# USB-PS2_v4_2.net
KiCad netlist of a schematic drawn in EAGLE
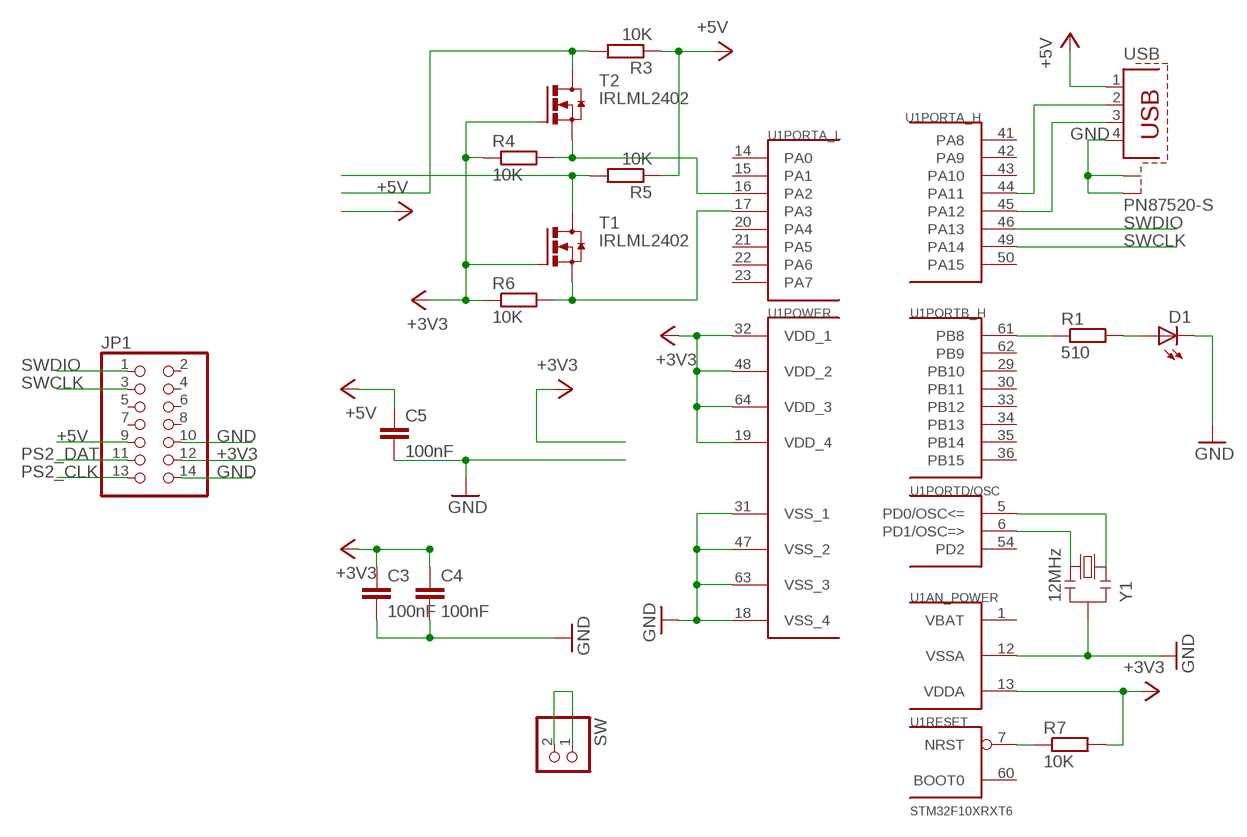
[diagram p0: schematic, sheet 1]

(export (version "E")
  (design (tool "Eeschema 10.0.6"))
  (components
    (comp (ref "C3")
      (value "100nF")
      (footprint "eagle-import:C0805")
      (libsource (lib "eagle-import") (part "C-EUC0805"))
    )
    (comp (ref "C4")
      (value "100nF")
      (footprint "eagle-import:C0805")
      (libsource (lib "eagle-import") (part "C-EUC0805"))
    )
    (comp (ref "C5")
      (value "100nF")
      (footprint "eagle-import:C0805")
      (libsource (lib "eagle-import") (part "C-EUC0805"))
    )
    (comp (ref "D1")
      (value "LEDSML0805")
      (footprint "eagle-import:SML0805")
      (libsource (lib "eagle-import") (part "LEDSML0805"))
    )
    (comp (ref "JP1")
      (value "PINHD-2X7")
      (footprint "eagle-import:2X07")
      (libsource (lib "eagle-import") (part "PINHD-2X7"))
    )
    (comp (ref "R1")
      (value "510")
      (footprint "eagle-import:R0805")
      (libsource (lib "eagle-import") (part "R-EU_R0805"))
    )
    (comp (ref "R3")
      (value "10K")
      (footprint "eagle-import:R0805")
      (libsource (lib "eagle-import") (part "R-EU_R0805"))
    )
    (comp (ref "R4")
      (value "10K")
      (footprint "eagle-import:R0805")
      (libsource (lib "eagle-import") (part "R-EU_R0805"))
    )
    (comp (ref "R5")
      (value "10K")
      (footprint "eagle-import:R0805")
      (libsource (lib "eagle-import") (part "R-EU_R0805"))
    )
    (comp (ref "R6")
      (value "10K")
      (footprint "eagle-import:R0805")
      (libsource (lib "eagle-import") (part "R-EU_R0805"))
    )
    (comp (ref "R7")
      (value "10K")
      (footprint "eagle-import:R0805")
      (libsource (lib "eagle-import") (part "R-EU_R0805"))
    )
    (comp (ref "SW")
      (value "PINHD-1X2")
      (footprint "eagle-import:1X02")
      (libsource (lib "eagle-import") (part "PINHD-1X2"))
    )
    (comp (ref "T1")
      (value "IRLML2402")
      (footprint "eagle-import:MICRO3")
      (libsource (lib "eagle-import") (part "IRLML2402"))
    )
    (comp (ref "T2")
      (value "IRLML2402")
      (footprint "eagle-import:MICRO3")
      (libsource (lib "eagle-import") (part "IRLML2402"))
    )
    (comp (ref "U1")
      (value "STM32F10XRXT6")
      (footprint "eagle-import:TQFP64")
      (libsource (lib "eagle-import") (part "STM32F10XRXT6"))
    )
    (comp (ref "USB")
      (value "PN87520-S")
      (footprint "eagle-import:PN87520-S")
      (libsource (lib "eagle-import") (part "PN87520-S"))
    )
    (comp (ref "Y1")
      (value "12MHz")
      (footprint "eagle-import:RESONATOR")
      (fields (field (name "PART_NUMBER") "CSTCE16M0V53-R0"))
      (libsource (lib "eagle-import") (part "0011_CSTCE16M0V53-R0"))
    )
  )
  (nets
    (net (code "1") (name "+3V3") (class "Default")
      (node (ref "C3") (pin "1") (pinfunction "1_1") (pintype "passive"))
      (node (ref "C4") (pin "1") (pinfunction "1_1") (pintype "passive"))
      (node (ref "JP1") (pin "12") (pinfunction "12_12") (pintype "passive"))
      (node (ref "R4") (pin "1") (pinfunction "1_1") (pintype "passive"))
      (node (ref "R6") (pin "1") (pinfunction "1_1") (pintype "passive"))
      (node (ref "R7") (pin "2") (pinfunction "2_2") (pintype "passive"))
      (node (ref "T1") (pin "1") (pinfunction "G_1") (pintype "passive"))
      (node (ref "T2") (pin "1") (pinfunction "G_1") (pintype "passive"))
      (node (ref "U1") (pin "13") (pinfunction "VDDA_13") (pintype "power_in"))
      (node (ref "U1") (pin "19") (pinfunction "VDD_4_19") (pintype "power_in"))
      (node (ref "U1") (pin "32") (pinfunction "VDD_1_32") (pintype "power_in"))
      (node (ref "U1") (pin "48") (pinfunction "VDD_2_48") (pintype "power_in"))
      (node (ref "U1") (pin "64") (pinfunction "VDD_3_64") (pintype "power_in"))
    )
    (net (code "2") (name "+5V") (class "Default")
      (node (ref "C5") (pin "1") (pinfunction "1_1") (pintype "passive"))
      (node (ref "JP1") (pin "9") (pinfunction "9_9") (pintype "passive"))
      (node (ref "R3") (pin "1") (pinfunction "1_1") (pintype "passive"))
      (node (ref "R5") (pin "1") (pinfunction "1_1") (pintype "passive"))
      (node (ref "USB") (pin "1") (pinfunction "1_1") (pintype "passive"))
    )
    (net (code "3") (name "/PS2_CLK") (class "Default")
      (node (ref "JP1") (pin "13") (pinfunction "13_13") (pintype "passive"))
      (node (ref "R5") (pin "2") (pinfunction "2_2") (pintype "passive"))
      (node (ref "T1") (pin "3") (pinfunction "D_3") (pintype "passive"))
    )
    (net (code "4") (name "/PS2_DAT") (class "Default")
      (node (ref "JP1") (pin "11") (pinfunction "11_11") (pintype "passive"))
      (node (ref "R3") (pin "2") (pinfunction "2_2") (pintype "passive"))
      (node (ref "T2") (pin "3") (pinfunction "D_3") (pintype "passive"))
    )
    (net (code "5") (name "/SWCLK") (class "Default")
      (node (ref "JP1") (pin "3") (pinfunction "3_3") (pintype "passive"))
      (node (ref "U1") (pin "49") (pinfunction "PA14_49") (pintype "bidirectional"))
    )
    (net (code "6") (name "/SWDIO") (class "Default")
      (node (ref "JP1") (pin "1") (pinfunction "1_1") (pintype "passive"))
      (node (ref "U1") (pin "46") (pinfunction "PA13_46") (pintype "bidirectional"))
    )
    (net (code "7") (name "/VBAT") (class "Default")
      (node (ref "U1") (pin "1") (pinfunction "VBAT_1") (pintype "power_in"))
    )
    (net (code "8") (name "GND") (class "Default")
      (node (ref "C3") (pin "2") (pinfunction "2_2") (pintype "passive"))
      (node (ref "C4") (pin "2") (pinfunction "2_2") (pintype "passive"))
      (node (ref "C5") (pin "2") (pinfunction "2_2") (pintype "passive"))
      (node (ref "D1") (pin "C") (pinfunction "C_C") (pintype "passive"))
      (node (ref "JP1") (pin "10") (pinfunction "10_10") (pintype "passive"))
      (node (ref "JP1") (pin "14") (pinfunction "14_14") (pintype "passive"))
      (node (ref "U1") (pin "12") (pinfunction "VSSA_12") (pintype "power_in"))
      (node (ref "U1") (pin "18") (pinfunction "VSS_4_18") (pintype "power_in"))
      (node (ref "U1") (pin "31") (pinfunction "VSS_1_31") (pintype "power_in"))
      (node (ref "U1") (pin "47") (pinfunction "VSS_2_47") (pintype "power_in"))
      (node (ref "U1") (pin "63") (pinfunction "VSS_3_63") (pintype "power_in"))
      (node (ref "USB") (pin "4") (pinfunction "4_4") (pintype "passive"))
      (node (ref "USB") (pin "S1") (pinfunction "S1_S1") (pintype "passive"))
      (node (ref "USB") (pin "S2") (pinfunction "S2_S2") (pintype "passive"))
      (node (ref "Y1") (pin "2") (pinfunction "2_2") (pintype "passive"))
    )
    (net (code "9") (name "Net-(D1-PadA)") (class "Default")
      (node (ref "D1") (pin "A") (pinfunction "A_A") (pintype "passive"))
      (node (ref "R1") (pin "2") (pinfunction "2_2") (pintype "passive"))
    )
    (net (code "10") (name "Net-(SW-Pad1)") (class "Default")
      (node (ref "SW") (pin "1") (pinfunction "1_1") (pintype "passive"))
      (node (ref "SW") (pin "2") (pinfunction "2_2") (pintype "passive"))
    )
    (net (code "11") (name "Net-(T1-S)") (class "Default")
      (node (ref "R6") (pin "2") (pinfunction "2_2") (pintype "passive"))
      (node (ref "T1") (pin "2") (pinfunction "S_2") (pintype "passive"))
      (node (ref "U1") (pin "17") (pinfunction "PA3_17") (pintype "bidirectional"))
    )
    (net (code "12") (name "Net-(T2-S)") (class "Default")
      (node (ref "R4") (pin "2") (pinfunction "2_2") (pintype "passive"))
      (node (ref "T2") (pin "2") (pinfunction "S_2") (pintype "passive"))
      (node (ref "U1") (pin "16") (pinfunction "PA2_16") (pintype "bidirectional"))
    )
    (net (code "13") (name "Net-(U1B-PA11)") (class "Default")
      (node (ref "U1") (pin "44") (pinfunction "PA11_44") (pintype "bidirectional"))
      (node (ref "USB") (pin "2") (pinfunction "2_2") (pintype "passive"))
    )
    (net (code "14") (name "Net-(U1B-PA12)") (class "Default")
      (node (ref "U1") (pin "45") (pinfunction "PA12_45") (pintype "bidirectional"))
      (node (ref "USB") (pin "3") (pinfunction "3_3") (pintype "passive"))
    )
    (net (code "15") (name "Net-(U1D-PB8)") (class "Default")
      (node (ref "R1") (pin "1") (pinfunction "1_1") (pintype "passive"))
      (node (ref "U1") (pin "61") (pinfunction "PB8_61") (pintype "bidirectional"))
    )
    (net (code "16") (name "Net-(U1H-PD0{slash}OSC<=)") (class "Default")
      (node (ref "U1") (pin "5") (pinfunction "PD0/OSC<=_5") (pintype "bidirectional"))
      (node (ref "Y1") (pin "1") (pinfunction "1_1") (pintype "passive"))
    )
    (net (code "17") (name "Net-(U1H-PD1{slash}OSC=>)") (class "Default")
      (node (ref "U1") (pin "6") (pinfunction "PD1/OSC=>_6") (pintype "bidirectional"))
      (node (ref "Y1") (pin "3") (pinfunction "3_3") (pintype "passive"))
    )
    (net (code "18") (name "Net-(U1J-NRST)") (class "Default")
      (node (ref "R7") (pin "1") (pinfunction "1_1") (pintype "passive"))
      (node (ref "U1") (pin "7") (pinfunction "NRST_7") (pintype "input"))
    )
    (net (code "19") (name "unconnected-(JP1-Pad2)") (class "Default")
      (node (ref "JP1") (pin "2") (pinfunction "2_2") (pintype "passive"))
    )
    (net (code "20") (name "unconnected-(JP1-Pad4)") (class "Default")
      (node (ref "JP1") (pin "4") (pinfunction "4_4") (pintype "passive"))
    )
    (net (code "21") (name "unconnected-(JP1-Pad5)") (class "Default")
      (node (ref "JP1") (pin "5") (pinfunction "5_5") (pintype "passive"))
    )
    (net (code "22") (name "unconnected-(JP1-Pad6)") (class "Default")
      (node (ref "JP1") (pin "6") (pinfunction "6_6") (pintype "passive"))
    )
    (net (code "23") (name "unconnected-(JP1-Pad7)") (class "Default")
      (node (ref "JP1") (pin "7") (pinfunction "7_7") (pintype "passive"))
    )
    (net (code "24") (name "unconnected-(JP1-Pad8)") (class "Default")
      (node (ref "JP1") (pin "8") (pinfunction "8_8") (pintype "passive"))
    )
    (net (code "25") (name "unconnected-(U1B-PA8-Pad41)") (class "Default")
      (node (ref "U1") (pin "41") (pinfunction "PA8_41") (pintype "bidirectional"))
    )
    (net (code "26") (name "unconnected-(U1B-PA9-Pad42)") (class "Default")
      (node (ref "U1") (pin "42") (pinfunction "PA9_42") (pintype "bidirectional"))
    )
    (net (code "27") (name "unconnected-(U1B-PA10-Pad43)") (class "Default")
      (node (ref "U1") (pin "43") (pinfunction "PA10_43") (pintype "bidirectional"))
    )
    (net (code "28") (name "unconnected-(U1B-PA15-Pad50)") (class "Default")
      (node (ref "U1") (pin "50") (pinfunction "PA15_50") (pintype "bidirectional"))
    )
    (net (code "29") (name "unconnected-(U1C-PA0-Pad14)") (class "Default")
      (node (ref "U1") (pin "14") (pinfunction "PA0_14") (pintype "bidirectional"))
    )
    (net (code "30") (name "unconnected-(U1C-PA1-Pad15)") (class "Default")
      (node (ref "U1") (pin "15") (pinfunction "PA1_15") (pintype "bidirectional"))
    )
    (net (code "31") (name "unconnected-(U1C-PA4-Pad20)") (class "Default")
      (node (ref "U1") (pin "20") (pinfunction "PA4_20") (pintype "bidirectional"))
    )
    (net (code "32") (name "unconnected-(U1C-PA5-Pad21)") (class "Default")
      (node (ref "U1") (pin "21") (pinfunction "PA5_21") (pintype "bidirectional"))
    )
    (net (code "33") (name "unconnected-(U1C-PA6-Pad22)") (class "Default")
      (node (ref "U1") (pin "22") (pinfunction "PA6_22") (pintype "bidirectional"))
    )
    (net (code "34") (name "unconnected-(U1C-PA7-Pad23)") (class "Default")
      (node (ref "U1") (pin "23") (pinfunction "PA7_23") (pintype "bidirectional"))
    )
    (net (code "35") (name "unconnected-(U1D-PB9-Pad62)") (class "Default")
      (node (ref "U1") (pin "62") (pinfunction "PB9_62") (pintype "bidirectional"))
    )
    (net (code "36") (name "unconnected-(U1D-PB10-Pad29)") (class "Default")
      (node (ref "U1") (pin "29") (pinfunction "PB10_29") (pintype "bidirectional"))
    )
    (net (code "37") (name "unconnected-(U1D-PB11-Pad30)") (class "Default")
      (node (ref "U1") (pin "30") (pinfunction "PB11_30") (pintype "bidirectional"))
    )
    (net (code "38") (name "unconnected-(U1D-PB12-Pad33)") (class "Default")
      (node (ref "U1") (pin "33") (pinfunction "PB12_33") (pintype "bidirectional"))
    )
    (net (code "39") (name "unconnected-(U1D-PB13-Pad34)") (class "Default")
      (node (ref "U1") (pin "34") (pinfunction "PB13_34") (pintype "bidirectional"))
    )
    (net (code "40") (name "unconnected-(U1D-PB14-Pad35)") (class "Default")
      (node (ref "U1") (pin "35") (pinfunction "PB14_35") (pintype "bidirectional"))
    )
    (net (code "41") (name "unconnected-(U1D-PB15-Pad36)") (class "Default")
      (node (ref "U1") (pin "36") (pinfunction "PB15_36") (pintype "bidirectional"))
    )
    (net (code "42") (name "unconnected-(U1H-PD2-Pad54)") (class "Default")
      (node (ref "U1") (pin "54") (pinfunction "PD2_54") (pintype "bidirectional"))
    )
    (net (code "43") (name "unconnected-(U1J-BOOT0-Pad60)") (class "Default")
      (node (ref "U1") (pin "60") (pinfunction "BOOT0_60") (pintype "input"))
    )
  )
)
